# Sensor_Breakout.net
KiCad netlist of a schematic drawn in EAGLE
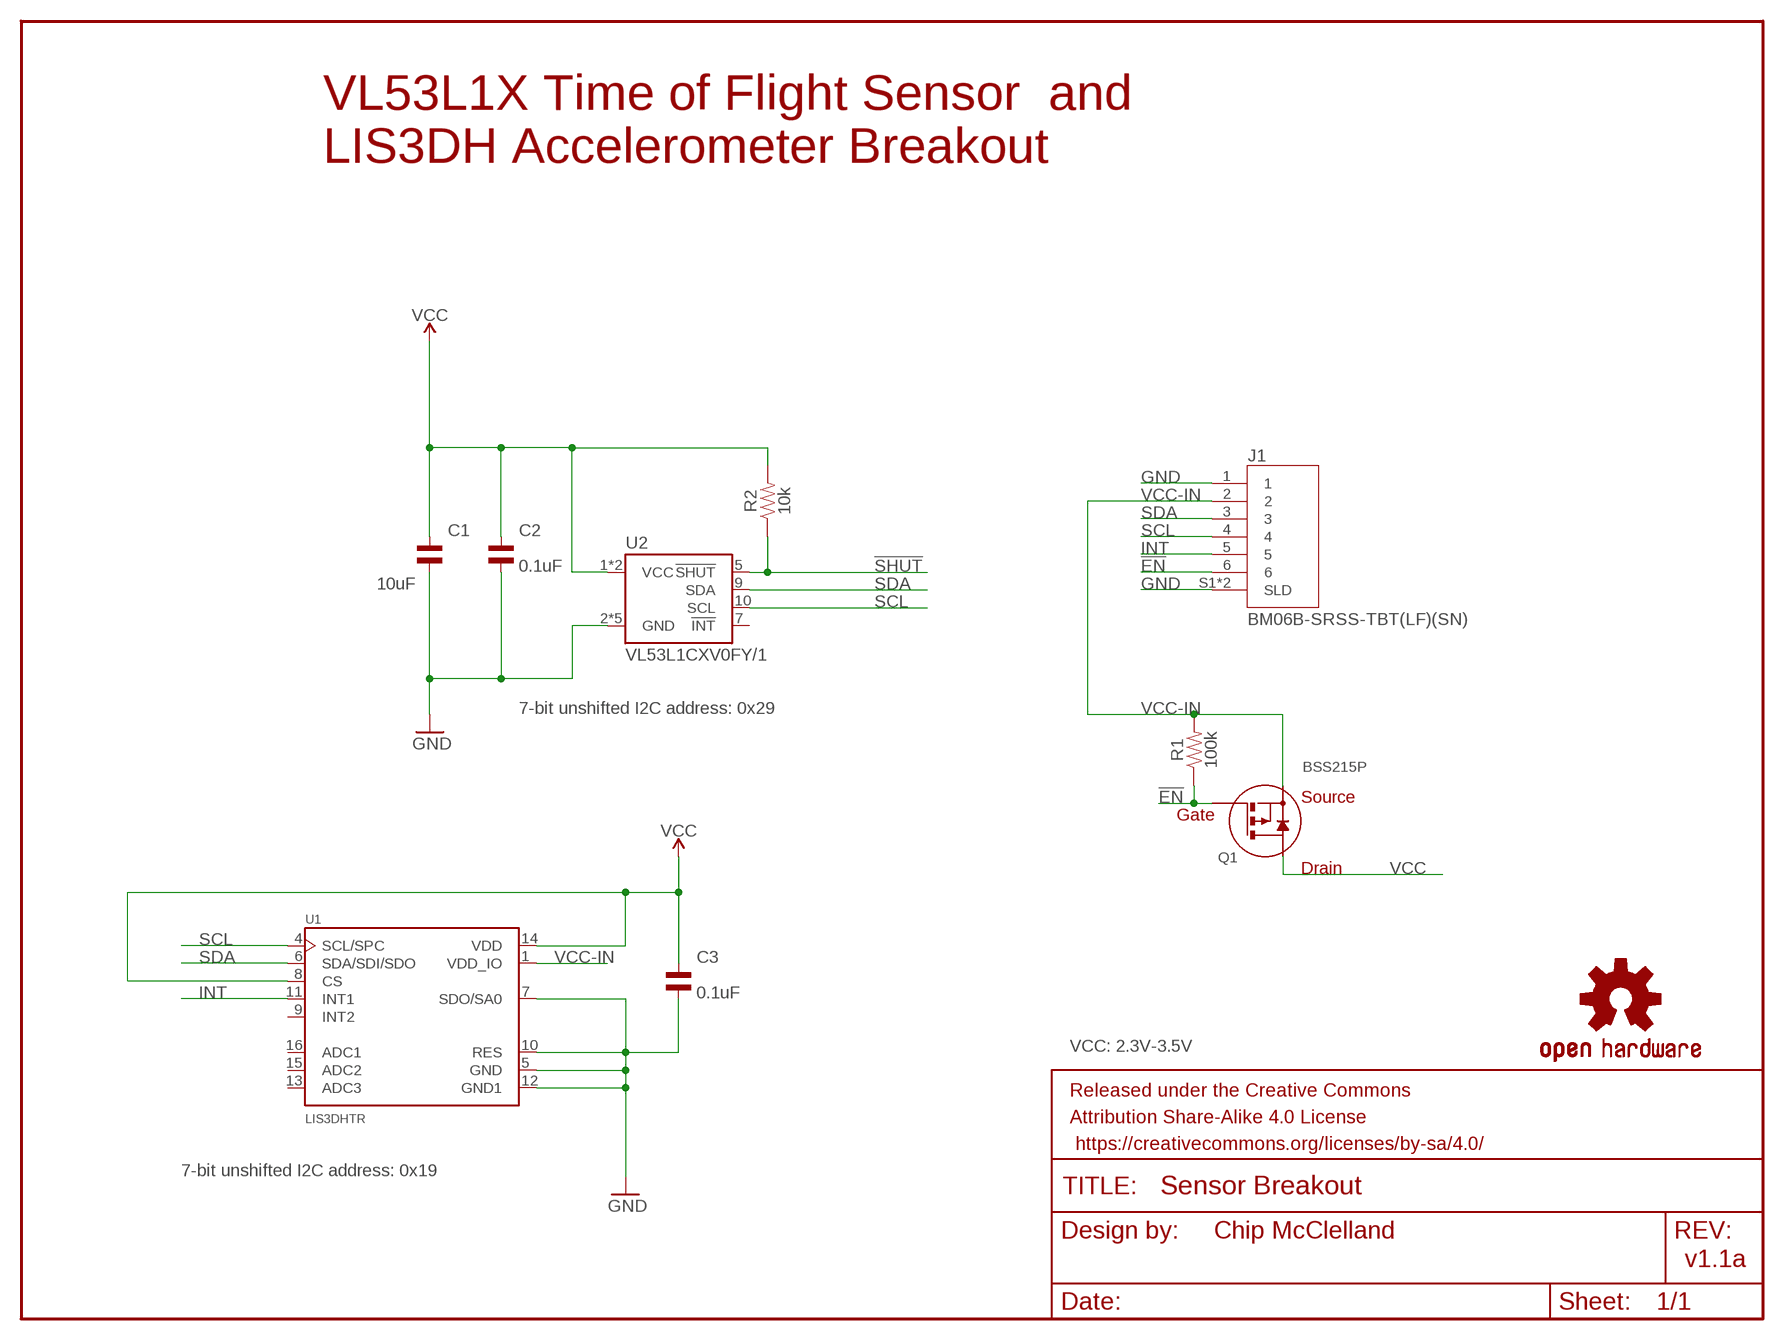
[diagram p0: schematic, sheet 1]

(export (version "E")
  (design (tool "Eeschema 10.0.6"))
  (components
    (comp (ref "C1")
      (value "10uF")
      (footprint "eagle-import:C1206")
      (fields
        (field (name "HOUSEPART") "Yes")
        (field (name "MPN") "MF-CAP-1206-10uF")
        (field (name "VOLTAGE") "16V")
      )
      (libsource (lib "eagle-import") (part "CAP-MF-10UF-1206"))
    )
    (comp (ref "C2")
      (value "0.1uF")
      (footprint "eagle-import:C0805")
      (fields
        (field (name "HOUSEPART") "YES")
        (field (name "MPN") "MF-CAP-0805-0.1uF")
        (field (name "VOLTAGE") "50V")
      )
      (libsource (lib "eagle-import") (part "CAP-MF-0.1UF-"))
    )
    (comp (ref "C3")
      (value "0.1uF")
      (footprint "eagle-import:C0805")
      (fields
        (field (name "HOUSEPART") "YES")
        (field (name "MPN") "MF-CAP-0805-0.1uF")
        (field (name "VOLTAGE") "50V")
      )
      (libsource (lib "eagle-import") (part "CAP-MF-0.1UF-"))
    )
    (comp (ref "FRAME1")
      (value "FRAME-LETTER")
      (footprint "eagle-import:CREATIVE_COMMONS")
      (fields (field (name "POPULATE") "0"))
      (libsource (lib "eagle-import") (part "FRAME-LETTER"))
    )
    (comp (ref "J1")
      (value "BM06B-SRSS-TBT(LF)(SN)")
      (footprint "eagle-import:JST_BM06B-SRSS-TB(LF)(SN)")
      (libsource (lib "eagle-import") (part "BM06B-SRSS-TBT(LF)(SN)"))
    )
    (comp (ref "LOGO1")
      (value "OSHW-LOGOMINI")
      (footprint "eagle-import:OSHW-LOGO-MINI")
      (libsource (lib "eagle-import") (part "OSHW-LOGOMINI"))
    )
    (comp (ref "Q1")
      (value "BSS215P")
      (footprint "eagle-import:SOT-23_3L_ONS-M")
      (fields (field (name "HOUSEPART") "No") (field (name "MPN") "BSS215PH6327XTSA1"))
      (libsource (lib "eagle-import") (part "BSS215P"))
    )
    (comp (ref "R1")
      (value "100k")
      (footprint "eagle-import:0805")
      (fields (field (name "MPN") "MF-RES-0805-100K") (field (name "MPN_1") "MF-RES-0805-100K"))
      (libsource (lib "eagle-import") (part "RESISTOR-MF-100K-0805"))
    )
    (comp (ref "R2")
      (value "10k")
      (footprint "eagle-import:0805")
      (fields (field (name "MPN") "MF-RES-0805-10K"))
      (libsource (lib "eagle-import") (part "RESISTOR-MF-10K-0805"))
    )
    (comp (ref "U1")
      (value "LIS3DHTR")
      (footprint "eagle-import:PQFN50P300X300X100-16N")
      (fields (field (name "MF") "STMicroelectronics") (field (name "MP") "LIS3DH"))
      (libsource (lib "eagle-import") (part "LIS3DH"))
    )
    (comp (ref "U2")
      (value "VL53L1CXV0FY/1")
      (footprint "eagle-import:VL53L1X")
      (libsource (lib "eagle-import") (part "VL53L1XSMD"))
    )
  )
  (nets
    (net (code "1") (name "/INT") (class "Default")
      (node (ref "J1") (pin "5") (pinfunction "5_5") (pintype "passive"))
      (node (ref "U1") (pin "11") (pinfunction "INT1_11") (pintype "input"))
    )
    (net (code "2") (name "/SCL") (class "Default")
      (node (ref "J1") (pin "4") (pinfunction "4_4") (pintype "passive"))
      (node (ref "U1") (pin "4") (pinfunction "SCL/SPC_4") (pintype "input"))
      (node (ref "U2") (pin "10") (pinfunction "SCL_10") (pintype "bidirectional"))
    )
    (net (code "3") (name "/SDA") (class "Default")
      (node (ref "J1") (pin "3") (pinfunction "3_3") (pintype "passive"))
      (node (ref "U1") (pin "6") (pinfunction "SDA/SDI/SDO_6") (pintype "input"))
      (node (ref "U2") (pin "9") (pinfunction "SDA_9") (pintype "bidirectional"))
    )
    (net (code "4") (name "/VCC-IN") (class "Default")
      (node (ref "J1") (pin "2") (pinfunction "2_2") (pintype "passive"))
      (node (ref "Q1") (pin "2") (pinfunction "SOURCE_2") (pintype "passive"))
      (node (ref "R1") (pin "2") (pinfunction "2_2") (pintype "passive"))
      (node (ref "U1") (pin "1") (pinfunction "VDD_IO_1") (pintype "power_in"))
    )
    (net (code "5") (name "/~{EN}") (class "Default")
      (node (ref "J1") (pin "6") (pinfunction "6_6") (pintype "passive"))
      (node (ref "Q1") (pin "1") (pinfunction "GATE_1") (pintype "passive"))
      (node (ref "R1") (pin "1") (pinfunction "1_1") (pintype "passive"))
    )
    (net (code "6") (name "/~{SHUT}") (class "Default")
      (node (ref "R2") (pin "1") (pinfunction "1_1") (pintype "passive"))
      (node (ref "U2") (pin "5") (pinfunction "~{SHUT}_5") (pintype "bidirectional"))
    )
    (net (code "7") (name "GND") (class "Default")
      (node (ref "C1") (pin "P$2") (pinfunction "P$2_P$2") (pintype "passive"))
      (node (ref "C2") (pin "P$2") (pinfunction "P$2_P$2") (pintype "passive"))
      (node (ref "C3") (pin "P$2") (pinfunction "P$2_P$2") (pintype "passive"))
      (node (ref "J1") (pin "1") (pinfunction "1_1") (pintype "passive"))
      (node (ref "J1") (pin "S1") (pinfunction "SLD_S1") (pintype "passive"))
      (node (ref "J1") (pin "S2") (pinfunction "SLD_S2") (pintype "passive"))
      (node (ref "U1") (pin "10") (pinfunction "RES_10") (pintype "power_in"))
      (node (ref "U1") (pin "12") (pinfunction "GND1_12") (pintype "power_in"))
      (node (ref "U1") (pin "5") (pinfunction "GND_5") (pintype "power_in"))
      (node (ref "U1") (pin "7") (pinfunction "SDO/SA0_7") (pintype "output"))
      (node (ref "U2") (pin "12") (pinfunction "GND_12") (pintype "bidirectional"))
      (node (ref "U2") (pin "2") (pinfunction "GND_2") (pintype "bidirectional"))
      (node (ref "U2") (pin "3") (pinfunction "GND_3") (pintype "bidirectional"))
      (node (ref "U2") (pin "4") (pinfunction "GND_4") (pintype "bidirectional"))
      (node (ref "U2") (pin "6") (pinfunction "GND_6") (pintype "bidirectional"))
    )
    (net (code "8") (name "VCC") (class "Default")
      (node (ref "C1") (pin "P$1") (pinfunction "P$1_P$1") (pintype "passive"))
      (node (ref "C2") (pin "P$1") (pinfunction "P$1_P$1") (pintype "passive"))
      (node (ref "C3") (pin "P$1") (pinfunction "P$1_P$1") (pintype "passive"))
      (node (ref "Q1") (pin "3") (pinfunction "DRAIN_3") (pintype "passive"))
      (node (ref "R2") (pin "2") (pinfunction "2_2") (pintype "passive"))
      (node (ref "U1") (pin "14") (pinfunction "VDD_14") (pintype "power_in"))
      (node (ref "U1") (pin "8") (pinfunction "CS_8") (pintype "input"))
      (node (ref "U2") (pin "1") (pinfunction "VCC_1") (pintype "bidirectional"))
      (node (ref "U2") (pin "11") (pinfunction "VCC_11") (pintype "bidirectional"))
    )
    (net (code "9") (name "unconnected-(U1-ADC1-Pad16)") (class "Default")
      (node (ref "U1") (pin "16") (pinfunction "ADC1_16") (pintype "input"))
    )
    (net (code "10") (name "unconnected-(U1-ADC2-Pad15)") (class "Default")
      (node (ref "U1") (pin "15") (pinfunction "ADC2_15") (pintype "input"))
    )
    (net (code "11") (name "unconnected-(U1-ADC3-Pad13)") (class "Default")
      (node (ref "U1") (pin "13") (pinfunction "ADC3_13") (pintype "input"))
    )
    (net (code "12") (name "unconnected-(U1-INT2-Pad9)") (class "Default")
      (node (ref "U1") (pin "9") (pinfunction "INT2_9") (pintype "input"))
    )
    (net (code "13") (name "unconnected-(U2-~{INT}-Pad7)") (class "Default")
      (node (ref "U2") (pin "7") (pinfunction "~{INT}_7") (pintype "bidirectional"))
    )
  )
)
